# breakoutboard.net
KiCad netlist of a schematic drawn in EAGLE
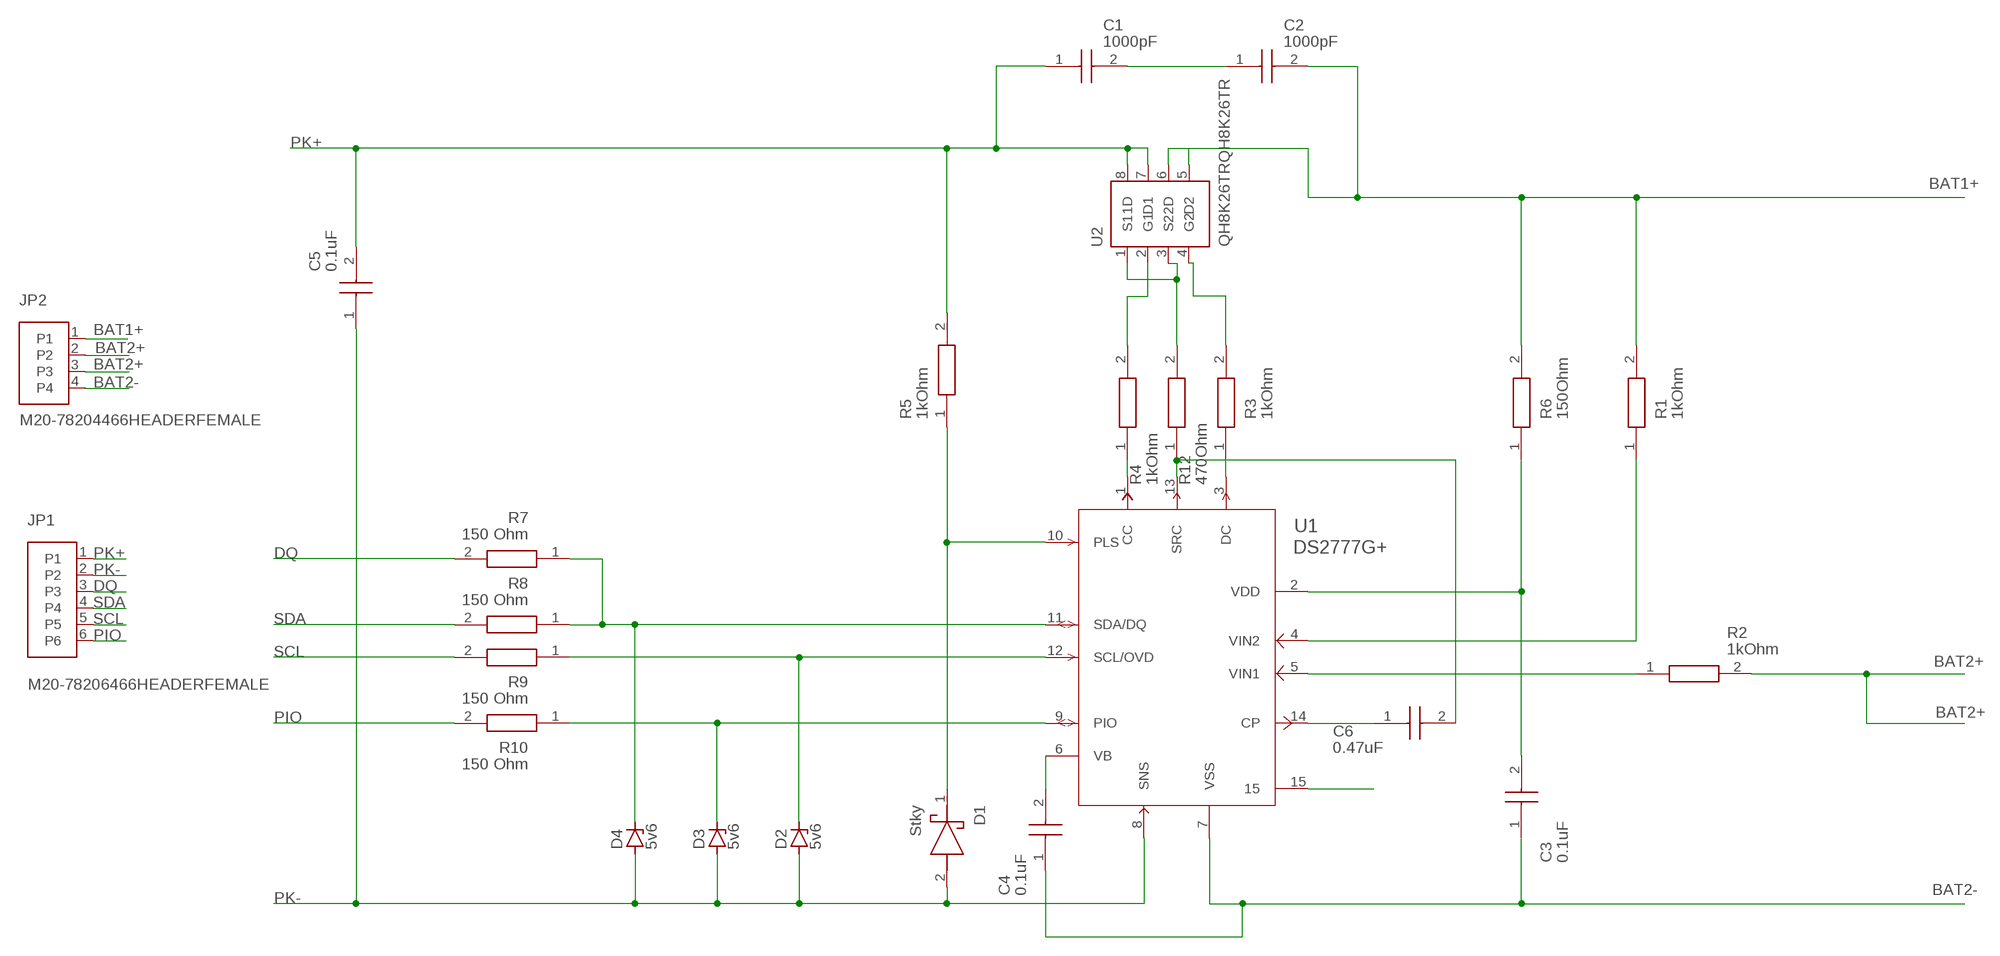
[diagram p0: schematic, sheet 1]

(export (version "E")
  (design (tool "Eeschema 10.0.6"))
  (components
    (comp (ref "C1")
      (value "1000pF")
      (footprint "eagle-import:CAPC2012X100N")
      (libsource (lib "eagle-import") (part "C0805C102J5G72101000PF"))
    )
    (comp (ref "C2")
      (value "1000pF")
      (footprint "eagle-import:CAPC2012X100N")
      (libsource (lib "eagle-import") (part "C0805C102J5G72101000PF"))
    )
    (comp (ref "C3")
      (value "0.1uF")
      (footprint "eagle-import:CAPC2012X100N")
      (libsource (lib "eagle-import") (part "C0805C104K5RAC74110.1UF"))
    )
    (comp (ref "C4")
      (value "0.1uF")
      (footprint "eagle-import:CAPC2012X100N")
      (libsource (lib "eagle-import") (part "C0805C104K5RAC74110.1UF"))
    )
    (comp (ref "C5")
      (value "0.1uF")
      (footprint "eagle-import:CAPC2012X100N")
      (libsource (lib "eagle-import") (part "C0805C104K5RAC74110.1UF"))
    )
    (comp (ref "C6")
      (value "0.47uF")
      (footprint "eagle-import:CAPC2012X100N")
      (libsource (lib "eagle-import") (part "C0805X474K5RACLR0.47UF"))
    )
    (comp (ref "D1")
      (value "Stky")
      (footprint "eagle-import:SOD3715X135N")
      (libsource (lib "eagle-import") (part "BAT54W-HG3-18SCHOTTKY"))
    )
    (comp (ref "D2")
      (value "5v6")
      (footprint "eagle-import:SODFL1608X75N")
      (libsource (lib "eagle-import") (part "BZX584C5V6-G3-08BZX584C5V6-G3-08"))
    )
    (comp (ref "D3")
      (value "5v6")
      (footprint "eagle-import:SODFL1608X75N")
      (libsource (lib "eagle-import") (part "BZX584C5V6-G3-08BZX584C5V6-G3-08"))
    )
    (comp (ref "D4")
      (value "5v6")
      (footprint "eagle-import:SODFL1608X75N")
      (libsource (lib "eagle-import") (part "BZX584C5V6-G3-08BZX584C5V6-G3-08"))
    )
    (comp (ref "JP1")
      (value "M20-78206466HEADERFEMALE")
      (footprint "eagle-import:HDRVR6W65P254_1X6_1564X250X865B")
      (libsource (lib "eagle-import") (part "M20-78206466HEADERFEMALE"))
    )
    (comp (ref "JP2")
      (value "M20-78204466HEADERFEMALE")
      (footprint "eagle-import:HDRVR4W65P254_1X4_1056X250X865B")
      (libsource (lib "eagle-import") (part "M20-78204466HEADERFEMALE"))
    )
    (comp (ref "R1")
      (value "1kOhm")
      (footprint "eagle-import:RESC2012X70N")
      (libsource (lib "eagle-import") (part "ERJ-P06D1500V150OHM"))
    )
    (comp (ref "R2")
      (value "1kOhm")
      (footprint "eagle-import:RESC2012X70N")
      (libsource (lib "eagle-import") (part "ERJ-P06D1500V150OHM"))
    )
    (comp (ref "R3")
      (value "1kOhm")
      (footprint "eagle-import:RESC2012X70N")
      (libsource (lib "eagle-import") (part "ERJ-P06D1500V150OHM"))
    )
    (comp (ref "R4")
      (value "1kOhm")
      (footprint "eagle-import:RESC2012X70N")
      (libsource (lib "eagle-import") (part "ERJ-P06D1500V150OHM"))
    )
    (comp (ref "R5")
      (value "1kOhm")
      (footprint "eagle-import:RESC2012X70N")
      (libsource (lib "eagle-import") (part "ERJ-P06D1500V150OHM"))
    )
    (comp (ref "R6")
      (value "150Ohm")
      (footprint "eagle-import:RESC2012X70N")
      (libsource (lib "eagle-import") (part "ERJ-P06F1001V"))
    )
    (comp (ref "R7")
      (value "150 Ohm")
      (footprint "eagle-import:RESC2012X70N")
      (libsource (lib "eagle-import") (part "ERJ-P06F1001V"))
    )
    (comp (ref "R8")
      (value "150 Ohm")
      (footprint "eagle-import:RESC2012X70N")
      (libsource (lib "eagle-import") (part "ERJ-P06F1001V"))
    )
    (comp (ref "R9")
      (value "150 Ohm")
      (footprint "eagle-import:RESC2012X70N")
      (libsource (lib "eagle-import") (part "ERJ-P06F1001V"))
    )
    (comp (ref "R10")
      (value "150 Ohm")
      (footprint "eagle-import:RESC2012X70N")
      (libsource (lib "eagle-import") (part "ERJ-P06F1001V"))
    )
    (comp (ref "R12")
      (value "470Ohm")
      (footprint "eagle-import:RESC2012X70N")
      (libsource (lib "eagle-import") (part "ERJ-UP6F4700V"))
    )
    (comp (ref "U1")
      (value "DS2777G+")
      (footprint "eagle-import:DS2777_TDFN-15-OWN")
      (libsource (lib "eagle-import") (part "DS2777G+"))
    )
    (comp (ref "U2")
      (value "QH8K26TRQH8K26TR")
      (footprint "eagle-import:SOTFL65P280X85-8N")
      (libsource (lib "eagle-import") (part "QH8K26TRQH8K26TR"))
    )
  )
  (nets
    (net (code "1") (name "/BAT1+") (class "Default")
      (node (ref "C2") (pin "2") (pinfunction "2_2") (pintype "bidirectional"))
      (node (ref "JP2") (pin "1") (pinfunction "P1_1") (pintype "bidirectional"))
      (node (ref "R1") (pin "2") (pinfunction "2_2") (pintype "bidirectional"))
      (node (ref "R6") (pin "2") (pinfunction "2_2") (pintype "bidirectional"))
      (node (ref "U2") (pin "5") (pinfunction "D2_5") (pintype "passive"))
      (node (ref "U2") (pin "6") (pinfunction "2D_6") (pintype "passive"))
    )
    (net (code "2") (name "/BAT2+") (class "Default")
      (node (ref "JP2") (pin "2") (pinfunction "P2_2") (pintype "bidirectional"))
      (node (ref "JP2") (pin "3") (pinfunction "P3_3") (pintype "bidirectional"))
      (node (ref "R2") (pin "2") (pinfunction "2_2") (pintype "bidirectional"))
    )
    (net (code "3") (name "/BAT2-") (class "Default")
      (node (ref "C3") (pin "1") (pinfunction "1_1") (pintype "bidirectional"))
      (node (ref "C4") (pin "1") (pinfunction "1_1") (pintype "bidirectional"))
      (node (ref "JP2") (pin "4") (pinfunction "P4_4") (pintype "bidirectional"))
      (node (ref "U1") (pin "15") (pinfunction "15_15") (pintype "passive"))
      (node (ref "U1") (pin "7") (pinfunction "VSS_7") (pintype "power_in"))
    )
    (net (code "4") (name "/DQ") (class "Default")
      (node (ref "JP1") (pin "3") (pinfunction "P3_3") (pintype "bidirectional"))
      (node (ref "R7") (pin "2") (pinfunction "2_2") (pintype "bidirectional"))
    )
    (net (code "5") (name "/PIO") (class "Default")
      (node (ref "JP1") (pin "6") (pinfunction "P6_6") (pintype "bidirectional"))
      (node (ref "R10") (pin "2") (pinfunction "2_2") (pintype "bidirectional"))
    )
    (net (code "6") (name "/PK+") (class "Default")
      (node (ref "C1") (pin "1") (pinfunction "1_1") (pintype "bidirectional"))
      (node (ref "C5") (pin "2") (pinfunction "2_2") (pintype "bidirectional"))
      (node (ref "JP1") (pin "1") (pinfunction "P1_1") (pintype "bidirectional"))
      (node (ref "R5") (pin "2") (pinfunction "2_2") (pintype "bidirectional"))
      (node (ref "U2") (pin "7") (pinfunction "D1_7") (pintype "passive"))
      (node (ref "U2") (pin "8") (pinfunction "1D_8") (pintype "passive"))
    )
    (net (code "7") (name "/PK-") (class "Default")
      (node (ref "C5") (pin "1") (pinfunction "1_1") (pintype "bidirectional"))
      (node (ref "D1") (pin "2") (pinfunction "A_2") (pintype "bidirectional"))
      (node (ref "D2") (pin "2") (pinfunction "A_2") (pintype "passive"))
      (node (ref "D3") (pin "2") (pinfunction "A_2") (pintype "passive"))
      (node (ref "D4") (pin "2") (pinfunction "A_2") (pintype "passive"))
      (node (ref "JP1") (pin "2") (pinfunction "P2_2") (pintype "bidirectional"))
      (node (ref "U1") (pin "8") (pinfunction "SNS_8") (pintype "input"))
    )
    (net (code "8") (name "/SCL") (class "Default")
      (node (ref "JP1") (pin "5") (pinfunction "P5_5") (pintype "bidirectional"))
      (node (ref "R9") (pin "2") (pinfunction "2_2") (pintype "bidirectional"))
    )
    (net (code "9") (name "/SDA") (class "Default")
      (node (ref "JP1") (pin "4") (pinfunction "P4_4") (pintype "bidirectional"))
      (node (ref "R8") (pin "2") (pinfunction "2_2") (pintype "bidirectional"))
    )
    (net (code "10") (name "Net-(C1-Pad2)") (class "Default")
      (node (ref "C1") (pin "2") (pinfunction "2_2") (pintype "bidirectional"))
      (node (ref "C2") (pin "1") (pinfunction "1_1") (pintype "bidirectional"))
    )
    (net (code "11") (name "Net-(D1-K)") (class "Default")
      (node (ref "D1") (pin "1") (pinfunction "K_1") (pintype "bidirectional"))
      (node (ref "R5") (pin "1") (pinfunction "1_1") (pintype "bidirectional"))
      (node (ref "U1") (pin "10") (pinfunction "PLS_10") (pintype "input"))
    )
    (net (code "12") (name "Net-(D2-K)") (class "Default")
      (node (ref "D2") (pin "1") (pinfunction "K_1") (pintype "passive"))
      (node (ref "R9") (pin "1") (pinfunction "1_1") (pintype "bidirectional"))
      (node (ref "U1") (pin "12") (pinfunction "SCL/OVD_12") (pintype "input"))
    )
    (net (code "13") (name "Net-(D3-K)") (class "Default")
      (node (ref "D3") (pin "1") (pinfunction "K_1") (pintype "passive"))
      (node (ref "R10") (pin "1") (pinfunction "1_1") (pintype "bidirectional"))
      (node (ref "U1") (pin "9") (pinfunction "PIO_9") (pintype "bidirectional"))
    )
    (net (code "14") (name "Net-(D4-K)") (class "Default")
      (node (ref "D4") (pin "1") (pinfunction "K_1") (pintype "passive"))
      (node (ref "R7") (pin "1") (pinfunction "1_1") (pintype "bidirectional"))
      (node (ref "R8") (pin "1") (pinfunction "1_1") (pintype "bidirectional"))
      (node (ref "U1") (pin "11") (pinfunction "SDA/DQ_11") (pintype "bidirectional"))
    )
    (net (code "15") (name "Net-(U1-CC)") (class "Default")
      (node (ref "R4") (pin "1") (pinfunction "1_1") (pintype "bidirectional"))
      (node (ref "U1") (pin "1") (pinfunction "CC_1") (pintype "output"))
    )
    (net (code "16") (name "Net-(U1-CP)") (class "Default")
      (node (ref "C6") (pin "1") (pinfunction "1_1") (pintype "bidirectional"))
      (node (ref "U1") (pin "14") (pinfunction "CP_14") (pintype "output"))
    )
    (net (code "17") (name "Net-(U1-DC)") (class "Default")
      (node (ref "R3") (pin "1") (pinfunction "1_1") (pintype "bidirectional"))
      (node (ref "U1") (pin "3") (pinfunction "DC_3") (pintype "output"))
    )
    (net (code "18") (name "Net-(U1-SRC)") (class "Default")
      (node (ref "C6") (pin "2") (pinfunction "2_2") (pintype "bidirectional"))
      (node (ref "R12") (pin "1") (pinfunction "1_1") (pintype "bidirectional"))
      (node (ref "U1") (pin "13") (pinfunction "SRC_13") (pintype "passive"))
    )
    (net (code "19") (name "Net-(U1-VB)") (class "Default")
      (node (ref "C4") (pin "2") (pinfunction "2_2") (pintype "bidirectional"))
      (node (ref "U1") (pin "6") (pinfunction "VB_6") (pintype "power_in"))
    )
    (net (code "20") (name "Net-(U1-VDD)") (class "Default")
      (node (ref "C3") (pin "2") (pinfunction "2_2") (pintype "bidirectional"))
      (node (ref "R6") (pin "1") (pinfunction "1_1") (pintype "bidirectional"))
      (node (ref "U1") (pin "2") (pinfunction "VDD_2") (pintype "power_in"))
    )
    (net (code "21") (name "Net-(U1-VIN1)") (class "Default")
      (node (ref "R2") (pin "1") (pinfunction "1_1") (pintype "bidirectional"))
      (node (ref "U1") (pin "5") (pinfunction "VIN1_5") (pintype "input"))
    )
    (net (code "22") (name "Net-(U1-VIN2)") (class "Default")
      (node (ref "R1") (pin "1") (pinfunction "1_1") (pintype "bidirectional"))
      (node (ref "U1") (pin "4") (pinfunction "VIN2_4") (pintype "input"))
    )
    (net (code "23") (name "Net-(U2-G1)") (class "Default")
      (node (ref "R4") (pin "2") (pinfunction "2_2") (pintype "bidirectional"))
      (node (ref "U2") (pin "2") (pinfunction "G1_2") (pintype "passive"))
    )
    (net (code "24") (name "Net-(U2-G2)") (class "Default")
      (node (ref "R3") (pin "2") (pinfunction "2_2") (pintype "bidirectional"))
      (node (ref "U2") (pin "4") (pinfunction "G2_4") (pintype "passive"))
    )
    (net (code "25") (name "Net-(U2-S1)") (class "Default")
      (node (ref "R12") (pin "2") (pinfunction "2_2") (pintype "bidirectional"))
      (node (ref "U2") (pin "1") (pinfunction "S1_1") (pintype "passive"))
      (node (ref "U2") (pin "3") (pinfunction "S2_3") (pintype "passive"))
    )
  )
)
